# Adafruit_ItsyBitsy_M0.net
KiCad netlist of a schematic drawn in EAGLE
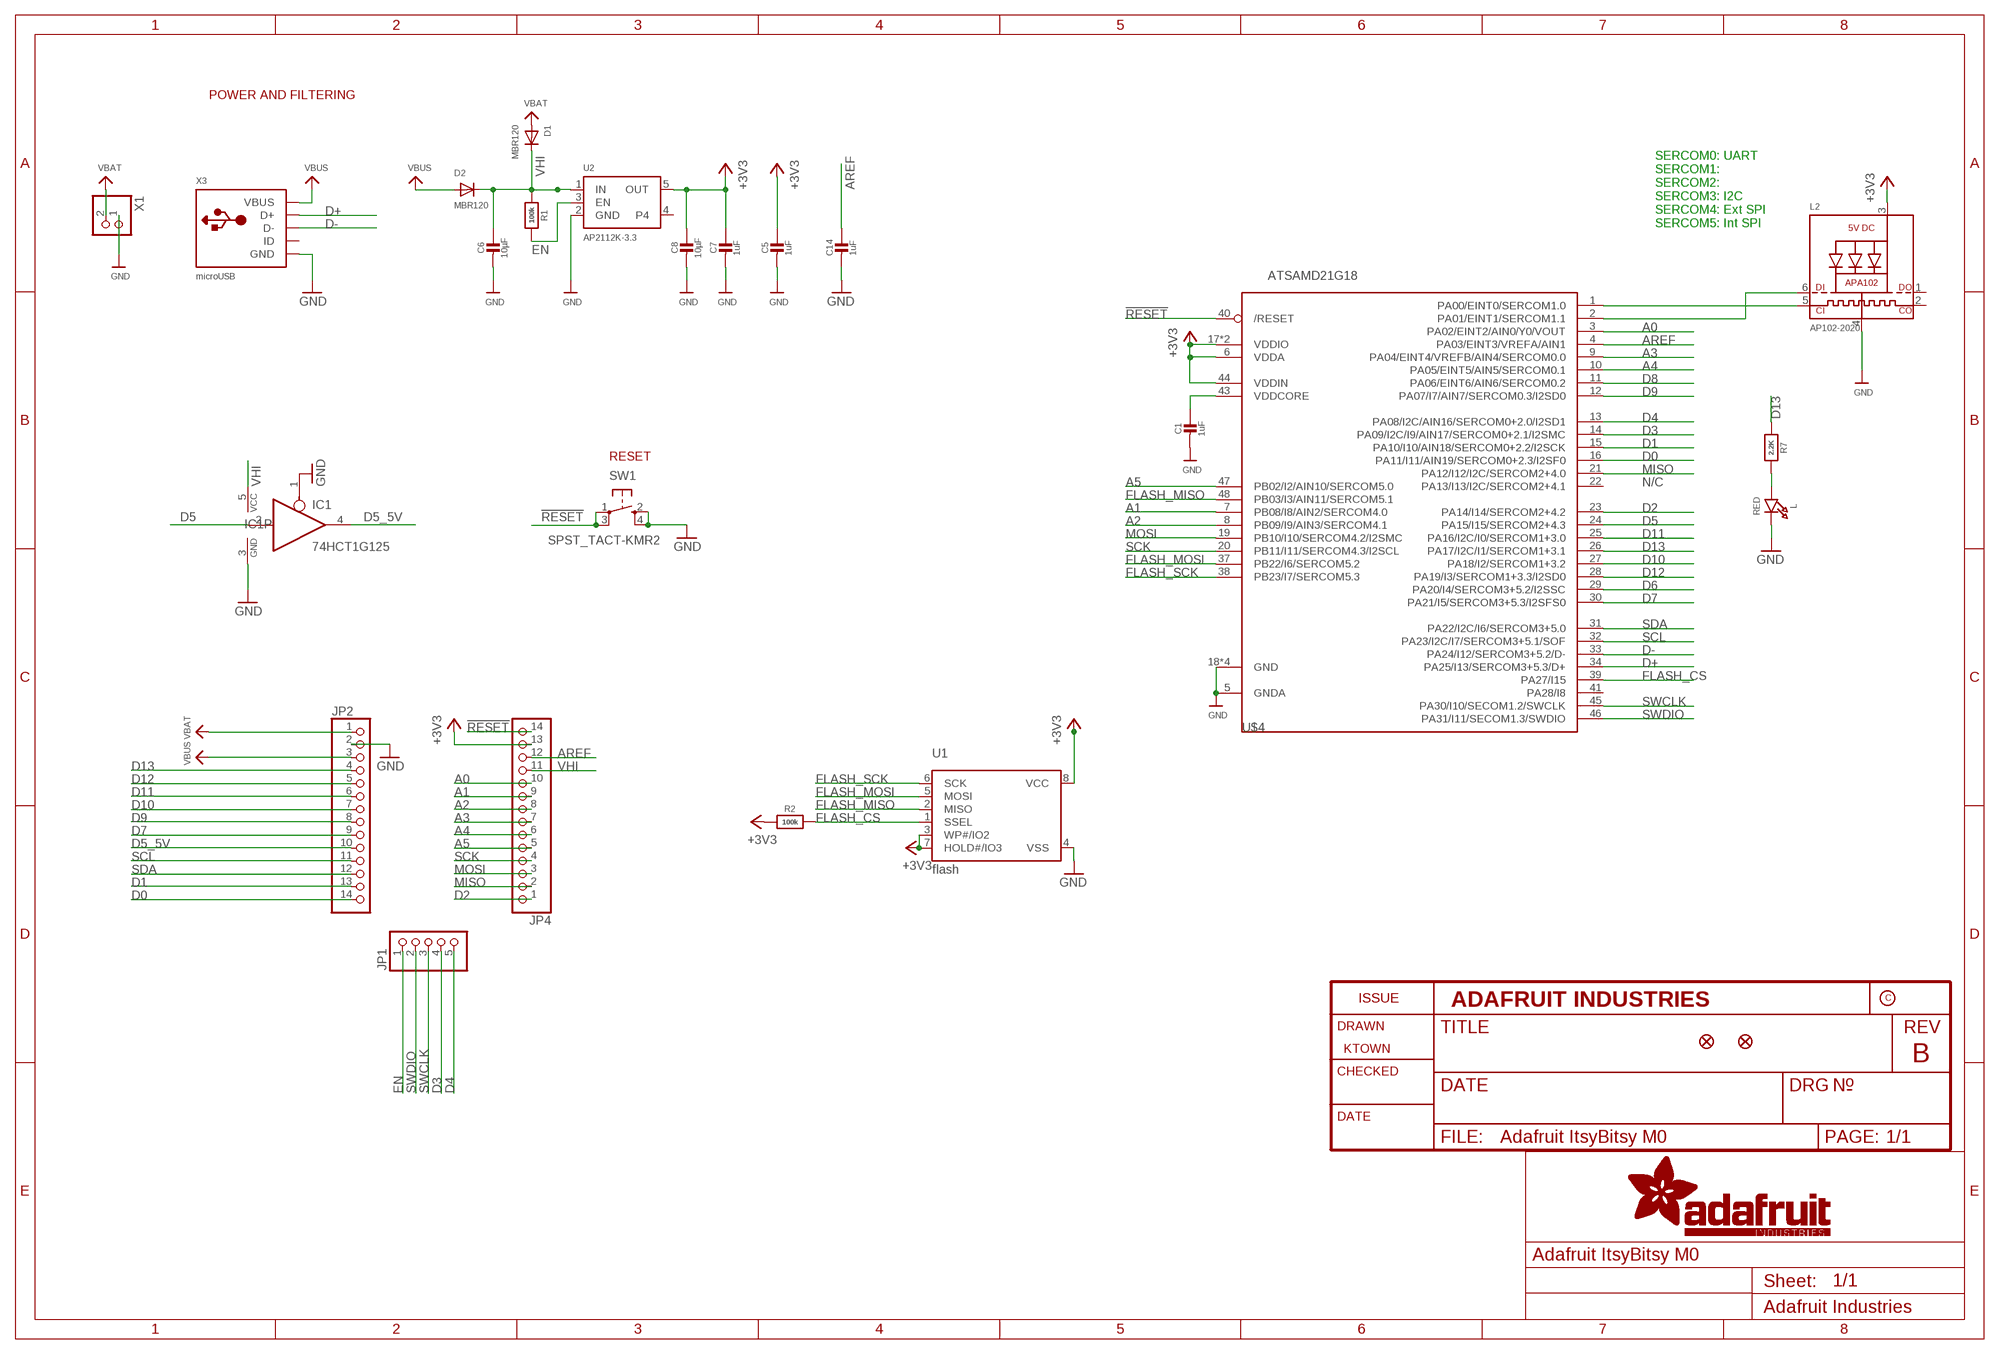
[diagram p0: schematic, sheet 1]

(export (version "E")
  (design (tool "Eeschema 10.0.6"))
  (components
    (comp (ref "C1")
      (value "1uF")
      (footprint "eagle-import:0603-NO")
      (libsource (lib "eagle-import") (part "CAP_CERAMIC0603_NO"))
    )
    (comp (ref "C5")
      (value "1uF")
      (footprint "eagle-import:0603-NO")
      (libsource (lib "eagle-import") (part "CAP_CERAMIC0603_NO"))
    )
    (comp (ref "C6")
      (value "10µF")
      (footprint "eagle-import:0805-NO")
      (libsource (lib "eagle-import") (part "CAP_CERAMIC0805-NOOUTLINE"))
    )
    (comp (ref "C7")
      (value "1uF")
      (footprint "eagle-import:0603-NO")
      (libsource (lib "eagle-import") (part "CAP_CERAMIC0603_NO"))
    )
    (comp (ref "C8")
      (value "10µF")
      (footprint "eagle-import:0805-NO")
      (libsource (lib "eagle-import") (part "CAP_CERAMIC0805-NOOUTLINE"))
    )
    (comp (ref "C14")
      (value "1uF")
      (footprint "eagle-import:0603-NO")
      (libsource (lib "eagle-import") (part "CAP_CERAMIC0603_NO"))
    )
    (comp (ref "D1")
      (value "MBR120")
      (footprint "eagle-import:SOD-123FL")
      (libsource (lib "eagle-import") (part "DIODE_SOD-123FL"))
    )
    (comp (ref "D2")
      (value "MBR120")
      (footprint "eagle-import:SOD-123FL")
      (libsource (lib "eagle-import") (part "DIODE_SOD-123FL"))
    )
    (comp (ref "IC1")
      (value "74HCT1G125")
      (footprint "eagle-import:SOT23-5")
      (libsource (lib "eagle-import") (part "741G125DBVAHC"))
    )
    (comp (ref "JP1")
      (value "HEADER-1X570MIL")
      (footprint "eagle-import:1X05_ROUND_70")
      (libsource (lib "eagle-import") (part "HEADER-1X570MIL"))
    )
    (comp (ref "JP2")
      (value "HEADER-1X14")
      (footprint "eagle-import:1X14_ROUND70")
      (libsource (lib "eagle-import") (part "HEADER-1X14"))
    )
    (comp (ref "JP4")
      (value "HEADER-1X14")
      (footprint "eagle-import:1X14_ROUND70")
      (libsource (lib "eagle-import") (part "HEADER-1X14"))
    )
    (comp (ref "L")
      (value "RED")
      (footprint "eagle-import:CHIPLED_0805_NOOUTLINE")
      (libsource (lib "eagle-import") (part "LED0805_NOOUTLINE"))
    )
    (comp (ref "L2")
      (value "AP102-2020")
      (footprint "eagle-import:APA102_2020")
      (libsource (lib "eagle-import") (part "APA1022020"))
    )
    (comp (ref "R1")
      (value "100k")
      (footprint "eagle-import:0603-NO")
      (libsource (lib "eagle-import") (part "RESISTOR_0603_NOOUT"))
    )
    (comp (ref "R2")
      (value "100k")
      (footprint "eagle-import:0603-NO")
      (libsource (lib "eagle-import") (part "RESISTOR_0603_NOOUT"))
    )
    (comp (ref "R7")
      (value "2.2K")
      (footprint "eagle-import:0603-NO")
      (libsource (lib "eagle-import") (part "RESISTOR_0603_NOOUT"))
    )
    (comp (ref "SW1")
      (value "SPST_TACT-KMR2")
      (footprint "eagle-import:KMR2")
      (libsource (lib "eagle-import") (part "SPST_TACT-KMR2"))
    )
    (comp (ref "U$4")
      (value "ATSAMD21G18")
      (footprint "eagle-import:TQFN48_7MM")
      (libsource (lib "eagle-import") (part "ATSAMD21G_QFN"))
    )
    (comp (ref "U$34")
      (value "FIDUCIAL_1MM")
      (footprint "eagle-import:FIDUCIAL_1MM")
      (libsource (lib "eagle-import") (part "FIDUCIAL_1MM"))
    )
    (comp (ref "U$35")
      (value "FIDUCIAL_1MM")
      (footprint "eagle-import:FIDUCIAL_1MM")
      (libsource (lib "eagle-import") (part "FIDUCIAL_1MM"))
    )
    (comp (ref "U1")
      (value "flash")
      (footprint "eagle-import:USON8")
      (libsource (lib "eagle-import") (part "SPIFLASH_8PINUX"))
    )
    (comp (ref "U2")
      (value "AP2112K-3.3")
      (footprint "eagle-import:SOT23-5")
      (libsource (lib "eagle-import") (part "VREG_SOT23-5"))
    )
    (comp (ref "X1")
      (value "CON_JST_PH_2PIN")
      (footprint "eagle-import:JSTPH2")
      (libsource (lib "eagle-import") (part "CON_JST_PH_2PIN"))
    )
    (comp (ref "X3")
      (value "microUSB")
      (footprint "eagle-import:4UCONN_20329_V2")
      (libsource (lib "eagle-import") (part "USB_MICRO_20329_V2"))
    )
  )
  (nets
    (net (code "1") (name "+3V3") (class "Default")
      (node (ref "C5") (pin "1") (pinfunction "1_1") (pintype "passive"))
      (node (ref "C7") (pin "1") (pinfunction "1_1") (pintype "passive"))
      (node (ref "C8") (pin "1") (pinfunction "1_1") (pintype "passive"))
      (node (ref "JP4") (pin "13") (pinfunction "13_13") (pintype "passive"))
      (node (ref "L2") (pin "3") (pinfunction "VDD_3") (pintype "power_in"))
      (node (ref "R2") (pin "1") (pinfunction "1_1") (pintype "passive"))
      (node (ref "U$4") (pin "17") (pinfunction "VDDIO_17") (pintype "power_in"))
      (node (ref "U$4") (pin "36") (pinfunction "VDDIO_36") (pintype "power_in"))
      (node (ref "U$4") (pin "44") (pinfunction "VDDIN_44") (pintype "power_in"))
      (node (ref "U$4") (pin "6") (pinfunction "VDDA_6") (pintype "power_in"))
      (node (ref "U1") (pin "3") (pinfunction "WP#/IO2_3") (pintype "bidirectional"))
      (node (ref "U1") (pin "7") (pinfunction "HOLD#/IO3_7") (pintype "bidirectional"))
      (node (ref "U1") (pin "8") (pinfunction "VCC_8") (pintype "bidirectional"))
      (node (ref "U2") (pin "5") (pinfunction "OUT_5") (pintype "power_in"))
    )
    (net (code "2") (name "/A0") (class "Default")
      (node (ref "JP4") (pin "10") (pinfunction "10_10") (pintype "passive"))
      (node (ref "U$4") (pin "3") (pinfunction "PA02/EINT2/AIN0/Y0/VOUT_3") (pintype "bidirectional"))
    )
    (net (code "3") (name "/A1") (class "Default")
      (node (ref "JP4") (pin "9") (pinfunction "9_9") (pintype "passive"))
      (node (ref "U$4") (pin "7") (pinfunction "PB08/I8/AIN2/SERCOM4.0_7") (pintype "bidirectional"))
    )
    (net (code "4") (name "/A2") (class "Default")
      (node (ref "JP4") (pin "8") (pinfunction "8_8") (pintype "passive"))
      (node (ref "U$4") (pin "8") (pinfunction "PB09/I9/AIN3/SERCOM4.1_8") (pintype "bidirectional"))
    )
    (net (code "5") (name "/A3") (class "Default")
      (node (ref "JP4") (pin "7") (pinfunction "7_7") (pintype "passive"))
      (node (ref "U$4") (pin "9") (pinfunction "PA04/EINT4/VREFB/AIN4/SERCOM0.0_9") (pintype "bidirectional"))
    )
    (net (code "6") (name "/A4") (class "Default")
      (node (ref "JP4") (pin "6") (pinfunction "6_6") (pintype "passive"))
      (node (ref "U$4") (pin "10") (pinfunction "PA05/EINT5/AIN5/SERCOM0.1_10") (pintype "bidirectional"))
    )
    (net (code "7") (name "/A5") (class "Default")
      (node (ref "JP4") (pin "5") (pinfunction "5_5") (pintype "passive"))
      (node (ref "U$4") (pin "47") (pinfunction "PB02/I2/AIN10/SERCOM5.0_47") (pintype "bidirectional"))
    )
    (net (code "8") (name "/AREF") (class "Default")
      (node (ref "C14") (pin "1") (pinfunction "1_1") (pintype "passive"))
      (node (ref "JP4") (pin "12") (pinfunction "12_12") (pintype "passive"))
      (node (ref "U$4") (pin "4") (pinfunction "PA03/EINT3/VREFA/AIN1_4") (pintype "bidirectional"))
    )
    (net (code "9") (name "/D+") (class "Default")
      (node (ref "U$4") (pin "34") (pinfunction "PA25/I13/SERCOM3+5.3/D+_34") (pintype "bidirectional"))
      (node (ref "X3") (pin "D+") (pinfunction "D+_D+") (pintype "bidirectional"))
    )
    (net (code "10") (name "/D-") (class "Default")
      (node (ref "U$4") (pin "33") (pinfunction "PA24/I12/SERCOM3+5.2/D-_33") (pintype "bidirectional"))
      (node (ref "X3") (pin "D-") (pinfunction "D-_D-") (pintype "bidirectional"))
    )
    (net (code "11") (name "/D0") (class "Default")
      (node (ref "JP2") (pin "14") (pinfunction "14_14") (pintype "passive"))
      (node (ref "U$4") (pin "16") (pinfunction "PA11/I11/AIN19/SERCOM0+2.3/I2SF0_16") (pintype "bidirectional"))
    )
    (net (code "12") (name "/D1") (class "Default")
      (node (ref "JP2") (pin "13") (pinfunction "13_13") (pintype "passive"))
      (node (ref "U$4") (pin "15") (pinfunction "PA10/I10/AIN18/SERCOM0+2.2/I2SCK_15") (pintype "bidirectional"))
    )
    (net (code "13") (name "/D2") (class "Default")
      (node (ref "JP4") (pin "1") (pinfunction "1_1") (pintype "passive"))
      (node (ref "U$4") (pin "23") (pinfunction "PA14/I14/SERCOM2+4.2_23") (pintype "bidirectional"))
    )
    (net (code "14") (name "/D3") (class "Default")
      (node (ref "JP1") (pin "4") (pinfunction "4_4") (pintype "passive"))
      (node (ref "U$4") (pin "14") (pinfunction "PA09/I2C/I9/AIN17/SERCOM0+2.1/I2SMC_14") (pintype "bidirectional"))
    )
    (net (code "15") (name "/D4") (class "Default")
      (node (ref "JP1") (pin "5") (pinfunction "5_5") (pintype "passive"))
      (node (ref "U$4") (pin "13") (pinfunction "PA08/I2C/AIN16/SERCOM0+2.0/I2SD1_13") (pintype "bidirectional"))
    )
    (net (code "16") (name "/D5") (class "Default")
      (node (ref "IC1") (pin "2") (pinfunction "I_2") (pintype "input"))
      (node (ref "U$4") (pin "24") (pinfunction "PA15/I15/SERCOM2+4.3_24") (pintype "bidirectional"))
    )
    (net (code "17") (name "/D5_5V") (class "Default")
      (node (ref "IC1") (pin "4") (pinfunction "O_4") (pintype "tri_state"))
      (node (ref "JP2") (pin "10") (pinfunction "10_10") (pintype "passive"))
    )
    (net (code "18") (name "/D6") (class "Default")
      (node (ref "U$4") (pin "29") (pinfunction "PA20/I4/SERCOM3+5.2/I2SSC_29") (pintype "bidirectional"))
    )
    (net (code "19") (name "/D7") (class "Default")
      (node (ref "JP2") (pin "9") (pinfunction "9_9") (pintype "passive"))
      (node (ref "U$4") (pin "30") (pinfunction "PA21/I5/SERCOM3+5.3/I2SFS0_30") (pintype "bidirectional"))
    )
    (net (code "20") (name "/D8") (class "Default")
      (node (ref "U$4") (pin "11") (pinfunction "PA06/EINT6/AIN6/SERCOM0.2_11") (pintype "bidirectional"))
    )
    (net (code "21") (name "/D9") (class "Default")
      (node (ref "JP2") (pin "8") (pinfunction "8_8") (pintype "passive"))
      (node (ref "U$4") (pin "12") (pinfunction "PA07/I7/AIN7/SERCOM0.3/I2SD0_12") (pintype "bidirectional"))
    )
    (net (code "22") (name "/D10") (class "Default")
      (node (ref "JP2") (pin "7") (pinfunction "7_7") (pintype "passive"))
      (node (ref "U$4") (pin "27") (pinfunction "PA18/I2/SERCOM1+3.2_27") (pintype "bidirectional"))
    )
    (net (code "23") (name "/D11") (class "Default")
      (node (ref "JP2") (pin "6") (pinfunction "6_6") (pintype "passive"))
      (node (ref "U$4") (pin "25") (pinfunction "PA16/I2C/I0/SERCOM1+3.0_25") (pintype "bidirectional"))
    )
    (net (code "24") (name "/D12") (class "Default")
      (node (ref "JP2") (pin "5") (pinfunction "5_5") (pintype "passive"))
      (node (ref "U$4") (pin "28") (pinfunction "PA19/I3/SERCOM1+3.3/I2SD0_28") (pintype "bidirectional"))
    )
    (net (code "25") (name "/D13") (class "Default")
      (node (ref "JP2") (pin "4") (pinfunction "4_4") (pintype "passive"))
      (node (ref "R7") (pin "1") (pinfunction "1_1") (pintype "passive"))
      (node (ref "U$4") (pin "26") (pinfunction "PA17/I2C/I1/SERCOM1+3.1_26") (pintype "bidirectional"))
    )
    (net (code "26") (name "/EN") (class "Default")
      (node (ref "JP1") (pin "1") (pinfunction "1_1") (pintype "passive"))
      (node (ref "R1") (pin "2") (pinfunction "2_2") (pintype "passive"))
      (node (ref "U2") (pin "3") (pinfunction "EN_3") (pintype "input"))
    )
    (net (code "27") (name "/FLASH_CS") (class "Default")
      (node (ref "R2") (pin "2") (pinfunction "2_2") (pintype "passive"))
      (node (ref "U$4") (pin "39") (pinfunction "PA27/I15_39") (pintype "bidirectional"))
      (node (ref "U1") (pin "1") (pinfunction "SSEL_1") (pintype "bidirectional"))
    )
    (net (code "28") (name "/FLASH_MISO") (class "Default")
      (node (ref "U$4") (pin "48") (pinfunction "PB03/I3/AIN11/SERCOM5.1_48") (pintype "bidirectional"))
      (node (ref "U1") (pin "2") (pinfunction "MISO_2") (pintype "bidirectional"))
    )
    (net (code "29") (name "/FLASH_MOSI") (class "Default")
      (node (ref "U$4") (pin "37") (pinfunction "PB22/I6/SERCOM5.2_37") (pintype "bidirectional"))
      (node (ref "U1") (pin "5") (pinfunction "MOSI_5") (pintype "bidirectional"))
    )
    (net (code "30") (name "/FLASH_SCK") (class "Default")
      (node (ref "U$4") (pin "38") (pinfunction "PB23/I7/SERCOM5.3_38") (pintype "bidirectional"))
      (node (ref "U1") (pin "6") (pinfunction "SCK_6") (pintype "bidirectional"))
    )
    (net (code "31") (name "/MISO") (class "Default")
      (node (ref "JP4") (pin "2") (pinfunction "2_2") (pintype "passive"))
      (node (ref "U$4") (pin "21") (pinfunction "PA12/I12/I2C/SERCOM2+4.0_21") (pintype "bidirectional"))
    )
    (net (code "32") (name "/MOSI") (class "Default")
      (node (ref "JP4") (pin "3") (pinfunction "3_3") (pintype "passive"))
      (node (ref "U$4") (pin "19") (pinfunction "PB10/I10/SERCOM4.2/I2SMC_19") (pintype "bidirectional"))
    )
    (net (code "33") (name "/SCK") (class "Default")
      (node (ref "JP4") (pin "4") (pinfunction "4_4") (pintype "passive"))
      (node (ref "U$4") (pin "20") (pinfunction "PB11/I11/SERCOM4.3/I2SCL_20") (pintype "bidirectional"))
    )
    (net (code "34") (name "/SCL") (class "Default")
      (node (ref "JP2") (pin "11") (pinfunction "11_11") (pintype "passive"))
      (node (ref "U$4") (pin "32") (pinfunction "PA23/I2C/I7/SERCOM3+5.1/SOF_32") (pintype "bidirectional"))
    )
    (net (code "35") (name "/SDA") (class "Default")
      (node (ref "JP2") (pin "12") (pinfunction "12_12") (pintype "passive"))
      (node (ref "U$4") (pin "31") (pinfunction "PA22/I2C/I6/SERCOM3+5.0_31") (pintype "bidirectional"))
    )
    (net (code "36") (name "/SWCLK") (class "Default")
      (node (ref "JP1") (pin "3") (pinfunction "3_3") (pintype "passive"))
      (node (ref "U$4") (pin "45") (pinfunction "PA30/I10/SECOM1.2/SWCLK_45") (pintype "bidirectional"))
    )
    (net (code "37") (name "/SWDIO") (class "Default")
      (node (ref "JP1") (pin "2") (pinfunction "2_2") (pintype "passive"))
      (node (ref "U$4") (pin "46") (pinfunction "PA31/I11/SECOM1.3/SWDIO_46") (pintype "bidirectional"))
    )
    (net (code "38") (name "/VHI") (class "Default")
      (node (ref "C6") (pin "1") (pinfunction "1_1") (pintype "passive"))
      (node (ref "D1") (pin "C") (pinfunction "C_C") (pintype "passive"))
      (node (ref "D2") (pin "C") (pinfunction "C_C") (pintype "passive"))
      (node (ref "IC1") (pin "5") (pinfunction "VCC_5") (pintype "power_in"))
      (node (ref "JP4") (pin "11") (pinfunction "11_11") (pintype "passive"))
      (node (ref "R1") (pin "1") (pinfunction "1_1") (pintype "passive"))
      (node (ref "U2") (pin "1") (pinfunction "IN_1") (pintype "power_in"))
    )
    (net (code "39") (name "/~{RESET}") (class "Default")
      (node (ref "JP4") (pin "14") (pinfunction "14_14") (pintype "passive"))
      (node (ref "SW1") (pin "1") (pinfunction "P_1") (pintype "passive"))
      (node (ref "SW1") (pin "3") (pinfunction "P1_3") (pintype "passive"))
      (node (ref "U$4") (pin "40") (pinfunction "/RESET_40") (pintype "bidirectional"))
    )
    (net (code "40") (name "GND") (class "Default")
      (node (ref "C1") (pin "2") (pinfunction "2_2") (pintype "passive"))
      (node (ref "C14") (pin "2") (pinfunction "2_2") (pintype "passive"))
      (node (ref "C5") (pin "2") (pinfunction "2_2") (pintype "passive"))
      (node (ref "C6") (pin "2") (pinfunction "2_2") (pintype "passive"))
      (node (ref "C7") (pin "2") (pinfunction "2_2") (pintype "passive"))
      (node (ref "C8") (pin "2") (pinfunction "2_2") (pintype "passive"))
      (node (ref "IC1") (pin "1") (pinfunction "OE_1") (pintype "input"))
      (node (ref "IC1") (pin "3") (pinfunction "GND_3") (pintype "power_in"))
      (node (ref "JP2") (pin "2") (pinfunction "2_2") (pintype "passive"))
      (node (ref "L") (pin "C") (pinfunction "C_C") (pintype "passive"))
      (node (ref "L2") (pin "4") (pinfunction "GND_4") (pintype "power_in"))
      (node (ref "SW1") (pin "2") (pinfunction "S_2") (pintype "passive"))
      (node (ref "SW1") (pin "4") (pinfunction "S1_4") (pintype "passive"))
      (node (ref "U$4") (pin "18") (pinfunction "GND_18") (pintype "power_in"))
      (node (ref "U$4") (pin "35") (pinfunction "GND_35") (pintype "power_in"))
      (node (ref "U$4") (pin "42") (pinfunction "GND_42") (pintype "power_in"))
      (node (ref "U$4") (pin "5") (pinfunction "GNDA_5") (pintype "power_in"))
      (node (ref "U$4") (pin "THERMAL") (pinfunction "GND_THERMAL") (pintype "power_in"))
      (node (ref "U1") (pin "4") (pinfunction "VSS_4") (pintype "bidirectional"))
      (node (ref "U2") (pin "2") (pinfunction "GND_2") (pintype "power_in"))
      (node (ref "X1") (pin "1") (pinfunction "1_1") (pintype "passive"))
      (node (ref "X3") (pin "BASE@1") (pinfunction "GND_BASE@1") (pintype "power_in"))
      (node (ref "X3") (pin "BASE@2") (pinfunction "GND_BASE@2") (pintype "power_in"))
      (node (ref "X3") (pin "GND") (pinfunction "GND_GND") (pintype "power_in"))
      (node (ref "X3") (pin "SPRT@1") (pinfunction "GND_SPRT@1") (pintype "power_in"))
      (node (ref "X3") (pin "SPRT@2") (pinfunction "GND_SPRT@2") (pintype "power_in"))
      (node (ref "X3") (pin "SPRT@3") (pinfunction "GND_SPRT@3") (pintype "power_in"))
      (node (ref "X3") (pin "SPRT@4") (pinfunction "GND_SPRT@4") (pintype "power_in"))
    )
    (net (code "41") (name "Net-(L-PadA)") (class "Default")
      (node (ref "L") (pin "A") (pinfunction "A_A") (pintype "passive"))
      (node (ref "R7") (pin "2") (pinfunction "2_2") (pintype "passive"))
    )
    (net (code "42") (name "Net-(L2-CKI)") (class "Default")
      (node (ref "L2") (pin "5") (pinfunction "CKI_5") (pintype "input"))
      (node (ref "U$4") (pin "1") (pinfunction "PA00/EINT0/SERCOM1.0_1") (pintype "bidirectional"))
    )
    (net (code "43") (name "Net-(L2-DI)") (class "Default")
      (node (ref "L2") (pin "6") (pinfunction "DI_6") (pintype "input"))
      (node (ref "U$4") (pin "2") (pinfunction "PA01/EINT1/SERCOM1.1_2") (pintype "bidirectional"))
    )
    (net (code "44") (name "Net-(U$4-VDDCORE)") (class "Default")
      (node (ref "C1") (pin "1") (pinfunction "1_1") (pintype "passive"))
      (node (ref "U$4") (pin "43") (pinfunction "VDDCORE_43") (pintype "power_in"))
    )
    (net (code "45") (name "VBAT") (class "Default")
      (node (ref "D1") (pin "A") (pinfunction "A_A") (pintype "passive"))
      (node (ref "JP2") (pin "1") (pinfunction "1_1") (pintype "passive"))
      (node (ref "X1") (pin "2") (pinfunction "2_2") (pintype "passive"))
    )
    (net (code "46") (name "VBUS") (class "Default")
      (node (ref "D2") (pin "A") (pinfunction "A_A") (pintype "passive"))
      (node (ref "JP2") (pin "3") (pinfunction "3_3") (pintype "passive"))
      (node (ref "X3") (pin "VBUS") (pinfunction "VBUS_VBUS") (pintype "power_in"))
    )
    (net (code "47") (name "unconnected-(L2-CKO-Pad2)") (class "Default")
      (node (ref "L2") (pin "2") (pinfunction "CKO_2") (pintype "output"))
    )
    (net (code "48") (name "unconnected-(L2-DO-Pad1)") (class "Default")
      (node (ref "L2") (pin "1") (pinfunction "DO_1") (pintype "output"))
    )
    (net (code "49") (name "unconnected-(U$4-PA13{slash}I13{slash}I2C{slash}SERCOM2+4.1-Pad22)") (class "Default")
      (node (ref "U$4") (pin "22") (pinfunction "PA13/I13/I2C/SERCOM2+4.1_22") (pintype "bidirectional"))
    )
    (net (code "50") (name "unconnected-(U$4-PA28{slash}I8-Pad41)") (class "Default")
      (node (ref "U$4") (pin "41") (pinfunction "PA28/I8_41") (pintype "bidirectional"))
    )
    (net (code "51") (name "unconnected-(U2-P4-Pad4)") (class "Default")
      (node (ref "U2") (pin "4") (pinfunction "P4_4") (pintype "bidirectional"))
    )
    (net (code "52") (name "unconnected-(X3-PadID)") (class "Default")
      (node (ref "X3") (pin "ID") (pinfunction "ID_ID") (pintype "bidirectional"))
    )
  )
)
